# SubBus4.net
KiCad netlist of a schematic drawn in Altium Designer
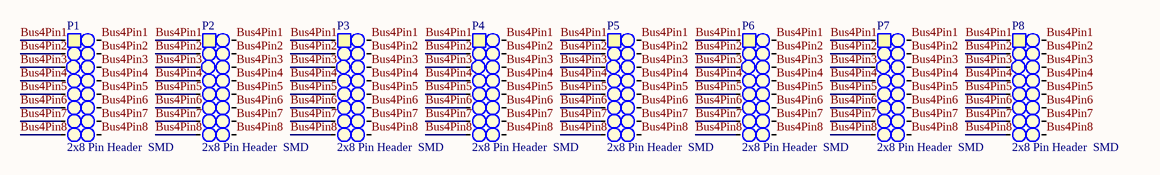
[diagram p0: SubBus4.SchDoc]

(export (version "E")
  (design (tool "Eeschema 10.0.6"))
  (components
    (comp (ref "P1")
      (value "2x8 Pin Header  SMD")
      (footprint "2X8_SMD_PH_2.54")
      (description "2.54mm, SMD")
      (libsource (lib "jclib") (part "2x8 Pin Header  SMD"))
    )
    (comp (ref "P2")
      (value "2x8 Pin Header  SMD")
      (footprint "2X8_SMD_PH_2.54")
      (description "2.54mm, SMD")
      (libsource (lib "jclib") (part "2x8 Pin Header  SMD"))
    )
    (comp (ref "P3")
      (value "2x8 Pin Header  SMD")
      (footprint "2X8_SMD_PH_2.54")
      (description "2.54mm, SMD")
      (libsource (lib "jclib") (part "2x8 Pin Header  SMD"))
    )
    (comp (ref "P4")
      (value "2x8 Pin Header  SMD")
      (footprint "2X8_SMD_PH_2.54")
      (description "2.54mm, SMD")
      (libsource (lib "jclib") (part "2x8 Pin Header  SMD"))
    )
    (comp (ref "P5")
      (value "2x8 Pin Header  SMD")
      (footprint "2X8_SMD_PH_2.54")
      (description "2.54mm, SMD")
      (libsource (lib "jclib") (part "2x8 Pin Header  SMD"))
    )
    (comp (ref "P6")
      (value "2x8 Pin Header  SMD")
      (footprint "2X8_SMD_PH_2.54")
      (description "2.54mm, SMD")
      (libsource (lib "jclib") (part "2x8 Pin Header  SMD"))
    )
    (comp (ref "P7")
      (value "2x8 Pin Header  SMD")
      (footprint "2X8_SMD_PH_2.54")
      (description "2.54mm, SMD")
      (libsource (lib "jclib") (part "2x8 Pin Header  SMD"))
    )
    (comp (ref "P8")
      (value "2x8 Pin Header  SMD")
      (footprint "2X8_SMD_PH_2.54")
      (description "2.54mm, SMD")
      (libsource (lib "jclib") (part "2x8 Pin Header  SMD"))
    )
  )
  (nets
    (net (code "1") (name "/Bus4Pin1") (class "Default")
      (node (ref "P1") (pin "1") (pinfunction "1_1") (pintype "passive"))
      (node (ref "P1") (pin "16") (pinfunction "16_16") (pintype "passive"))
      (node (ref "P2") (pin "1") (pinfunction "1_1") (pintype "passive"))
      (node (ref "P2") (pin "16") (pinfunction "16_16") (pintype "passive"))
      (node (ref "P3") (pin "1") (pinfunction "1_1") (pintype "passive"))
      (node (ref "P3") (pin "16") (pinfunction "16_16") (pintype "passive"))
      (node (ref "P4") (pin "1") (pinfunction "1_1") (pintype "passive"))
      (node (ref "P4") (pin "16") (pinfunction "16_16") (pintype "passive"))
      (node (ref "P5") (pin "1") (pinfunction "1_1") (pintype "passive"))
      (node (ref "P5") (pin "16") (pinfunction "16_16") (pintype "passive"))
      (node (ref "P6") (pin "1") (pinfunction "1_1") (pintype "passive"))
      (node (ref "P6") (pin "16") (pinfunction "16_16") (pintype "passive"))
      (node (ref "P7") (pin "1") (pinfunction "1_1") (pintype "passive"))
      (node (ref "P7") (pin "16") (pinfunction "16_16") (pintype "passive"))
      (node (ref "P8") (pin "1") (pinfunction "1_1") (pintype "passive"))
      (node (ref "P8") (pin "16") (pinfunction "16_16") (pintype "passive"))
    )
    (net (code "2") (name "/Bus4Pin2") (class "Default")
      (node (ref "P1") (pin "15") (pinfunction "15_15") (pintype "passive"))
      (node (ref "P1") (pin "2") (pinfunction "2_2") (pintype "passive"))
      (node (ref "P2") (pin "15") (pinfunction "15_15") (pintype "passive"))
      (node (ref "P2") (pin "2") (pinfunction "2_2") (pintype "passive"))
      (node (ref "P3") (pin "15") (pinfunction "15_15") (pintype "passive"))
      (node (ref "P3") (pin "2") (pinfunction "2_2") (pintype "passive"))
      (node (ref "P4") (pin "15") (pinfunction "15_15") (pintype "passive"))
      (node (ref "P4") (pin "2") (pinfunction "2_2") (pintype "passive"))
      (node (ref "P5") (pin "15") (pinfunction "15_15") (pintype "passive"))
      (node (ref "P5") (pin "2") (pinfunction "2_2") (pintype "passive"))
      (node (ref "P6") (pin "15") (pinfunction "15_15") (pintype "passive"))
      (node (ref "P6") (pin "2") (pinfunction "2_2") (pintype "passive"))
      (node (ref "P7") (pin "15") (pinfunction "15_15") (pintype "passive"))
      (node (ref "P7") (pin "2") (pinfunction "2_2") (pintype "passive"))
      (node (ref "P8") (pin "15") (pinfunction "15_15") (pintype "passive"))
      (node (ref "P8") (pin "2") (pinfunction "2_2") (pintype "passive"))
    )
    (net (code "3") (name "/Bus4Pin3") (class "Default")
      (node (ref "P1") (pin "14") (pinfunction "14_14") (pintype "passive"))
      (node (ref "P1") (pin "3") (pinfunction "3_3") (pintype "passive"))
      (node (ref "P2") (pin "14") (pinfunction "14_14") (pintype "passive"))
      (node (ref "P2") (pin "3") (pinfunction "3_3") (pintype "passive"))
      (node (ref "P3") (pin "14") (pinfunction "14_14") (pintype "passive"))
      (node (ref "P3") (pin "3") (pinfunction "3_3") (pintype "passive"))
      (node (ref "P4") (pin "14") (pinfunction "14_14") (pintype "passive"))
      (node (ref "P4") (pin "3") (pinfunction "3_3") (pintype "passive"))
      (node (ref "P5") (pin "14") (pinfunction "14_14") (pintype "passive"))
      (node (ref "P5") (pin "3") (pinfunction "3_3") (pintype "passive"))
      (node (ref "P6") (pin "14") (pinfunction "14_14") (pintype "passive"))
      (node (ref "P6") (pin "3") (pinfunction "3_3") (pintype "passive"))
      (node (ref "P7") (pin "14") (pinfunction "14_14") (pintype "passive"))
      (node (ref "P7") (pin "3") (pinfunction "3_3") (pintype "passive"))
      (node (ref "P8") (pin "14") (pinfunction "14_14") (pintype "passive"))
      (node (ref "P8") (pin "3") (pinfunction "3_3") (pintype "passive"))
    )
    (net (code "4") (name "/Bus4Pin4") (class "Default")
      (node (ref "P1") (pin "13") (pinfunction "13_13") (pintype "passive"))
      (node (ref "P1") (pin "4") (pinfunction "4_4") (pintype "passive"))
      (node (ref "P2") (pin "13") (pinfunction "13_13") (pintype "passive"))
      (node (ref "P2") (pin "4") (pinfunction "4_4") (pintype "passive"))
      (node (ref "P3") (pin "13") (pinfunction "13_13") (pintype "passive"))
      (node (ref "P3") (pin "4") (pinfunction "4_4") (pintype "passive"))
      (node (ref "P4") (pin "13") (pinfunction "13_13") (pintype "passive"))
      (node (ref "P4") (pin "4") (pinfunction "4_4") (pintype "passive"))
      (node (ref "P5") (pin "13") (pinfunction "13_13") (pintype "passive"))
      (node (ref "P5") (pin "4") (pinfunction "4_4") (pintype "passive"))
      (node (ref "P6") (pin "13") (pinfunction "13_13") (pintype "passive"))
      (node (ref "P6") (pin "4") (pinfunction "4_4") (pintype "passive"))
      (node (ref "P7") (pin "13") (pinfunction "13_13") (pintype "passive"))
      (node (ref "P7") (pin "4") (pinfunction "4_4") (pintype "passive"))
      (node (ref "P8") (pin "13") (pinfunction "13_13") (pintype "passive"))
      (node (ref "P8") (pin "4") (pinfunction "4_4") (pintype "passive"))
    )
    (net (code "5") (name "/Bus4Pin5") (class "Default")
      (node (ref "P1") (pin "12") (pinfunction "12_12") (pintype "passive"))
      (node (ref "P1") (pin "5") (pinfunction "5_5") (pintype "passive"))
      (node (ref "P2") (pin "12") (pinfunction "12_12") (pintype "passive"))
      (node (ref "P2") (pin "5") (pinfunction "5_5") (pintype "passive"))
      (node (ref "P3") (pin "12") (pinfunction "12_12") (pintype "passive"))
      (node (ref "P3") (pin "5") (pinfunction "5_5") (pintype "passive"))
      (node (ref "P4") (pin "12") (pinfunction "12_12") (pintype "passive"))
      (node (ref "P4") (pin "5") (pinfunction "5_5") (pintype "passive"))
      (node (ref "P5") (pin "12") (pinfunction "12_12") (pintype "passive"))
      (node (ref "P5") (pin "5") (pinfunction "5_5") (pintype "passive"))
      (node (ref "P6") (pin "12") (pinfunction "12_12") (pintype "passive"))
      (node (ref "P6") (pin "5") (pinfunction "5_5") (pintype "passive"))
      (node (ref "P7") (pin "12") (pinfunction "12_12") (pintype "passive"))
      (node (ref "P7") (pin "5") (pinfunction "5_5") (pintype "passive"))
      (node (ref "P8") (pin "12") (pinfunction "12_12") (pintype "passive"))
      (node (ref "P8") (pin "5") (pinfunction "5_5") (pintype "passive"))
    )
    (net (code "6") (name "/Bus4Pin6") (class "Default")
      (node (ref "P1") (pin "11") (pinfunction "11_11") (pintype "passive"))
      (node (ref "P1") (pin "6") (pinfunction "6_6") (pintype "passive"))
      (node (ref "P2") (pin "11") (pinfunction "11_11") (pintype "passive"))
      (node (ref "P2") (pin "6") (pinfunction "6_6") (pintype "passive"))
      (node (ref "P3") (pin "11") (pinfunction "11_11") (pintype "passive"))
      (node (ref "P3") (pin "6") (pinfunction "6_6") (pintype "passive"))
      (node (ref "P4") (pin "11") (pinfunction "11_11") (pintype "passive"))
      (node (ref "P4") (pin "6") (pinfunction "6_6") (pintype "passive"))
      (node (ref "P5") (pin "11") (pinfunction "11_11") (pintype "passive"))
      (node (ref "P5") (pin "6") (pinfunction "6_6") (pintype "passive"))
      (node (ref "P6") (pin "11") (pinfunction "11_11") (pintype "passive"))
      (node (ref "P6") (pin "6") (pinfunction "6_6") (pintype "passive"))
      (node (ref "P7") (pin "11") (pinfunction "11_11") (pintype "passive"))
      (node (ref "P7") (pin "6") (pinfunction "6_6") (pintype "passive"))
      (node (ref "P8") (pin "11") (pinfunction "11_11") (pintype "passive"))
      (node (ref "P8") (pin "6") (pinfunction "6_6") (pintype "passive"))
    )
    (net (code "7") (name "/Bus4Pin7") (class "Default")
      (node (ref "P1") (pin "10") (pinfunction "10_10") (pintype "passive"))
      (node (ref "P1") (pin "7") (pinfunction "7_7") (pintype "passive"))
      (node (ref "P2") (pin "10") (pinfunction "10_10") (pintype "passive"))
      (node (ref "P2") (pin "7") (pinfunction "7_7") (pintype "passive"))
      (node (ref "P3") (pin "10") (pinfunction "10_10") (pintype "passive"))
      (node (ref "P3") (pin "7") (pinfunction "7_7") (pintype "passive"))
      (node (ref "P4") (pin "10") (pinfunction "10_10") (pintype "passive"))
      (node (ref "P4") (pin "7") (pinfunction "7_7") (pintype "passive"))
      (node (ref "P5") (pin "10") (pinfunction "10_10") (pintype "passive"))
      (node (ref "P5") (pin "7") (pinfunction "7_7") (pintype "passive"))
      (node (ref "P6") (pin "10") (pinfunction "10_10") (pintype "passive"))
      (node (ref "P6") (pin "7") (pinfunction "7_7") (pintype "passive"))
      (node (ref "P7") (pin "10") (pinfunction "10_10") (pintype "passive"))
      (node (ref "P7") (pin "7") (pinfunction "7_7") (pintype "passive"))
      (node (ref "P8") (pin "10") (pinfunction "10_10") (pintype "passive"))
      (node (ref "P8") (pin "7") (pinfunction "7_7") (pintype "passive"))
    )
    (net (code "8") (name "/Bus4Pin8") (class "Default")
      (node (ref "P1") (pin "8") (pinfunction "8_8") (pintype "passive"))
      (node (ref "P1") (pin "9") (pinfunction "9_9") (pintype "passive"))
      (node (ref "P2") (pin "8") (pinfunction "8_8") (pintype "passive"))
      (node (ref "P2") (pin "9") (pinfunction "9_9") (pintype "passive"))
      (node (ref "P3") (pin "8") (pinfunction "8_8") (pintype "passive"))
      (node (ref "P3") (pin "9") (pinfunction "9_9") (pintype "passive"))
      (node (ref "P4") (pin "8") (pinfunction "8_8") (pintype "passive"))
      (node (ref "P4") (pin "9") (pinfunction "9_9") (pintype "passive"))
      (node (ref "P5") (pin "8") (pinfunction "8_8") (pintype "passive"))
      (node (ref "P5") (pin "9") (pinfunction "9_9") (pintype "passive"))
      (node (ref "P6") (pin "8") (pinfunction "8_8") (pintype "passive"))
      (node (ref "P6") (pin "9") (pinfunction "9_9") (pintype "passive"))
      (node (ref "P7") (pin "8") (pinfunction "8_8") (pintype "passive"))
      (node (ref "P7") (pin "9") (pinfunction "9_9") (pintype "passive"))
      (node (ref "P8") (pin "8") (pinfunction "8_8") (pintype "passive"))
      (node (ref "P8") (pin "9") (pinfunction "9_9") (pintype "passive"))
    )
  )
)
